# IRIS.net
KiCad netlist of a schematic drawn in EAGLE
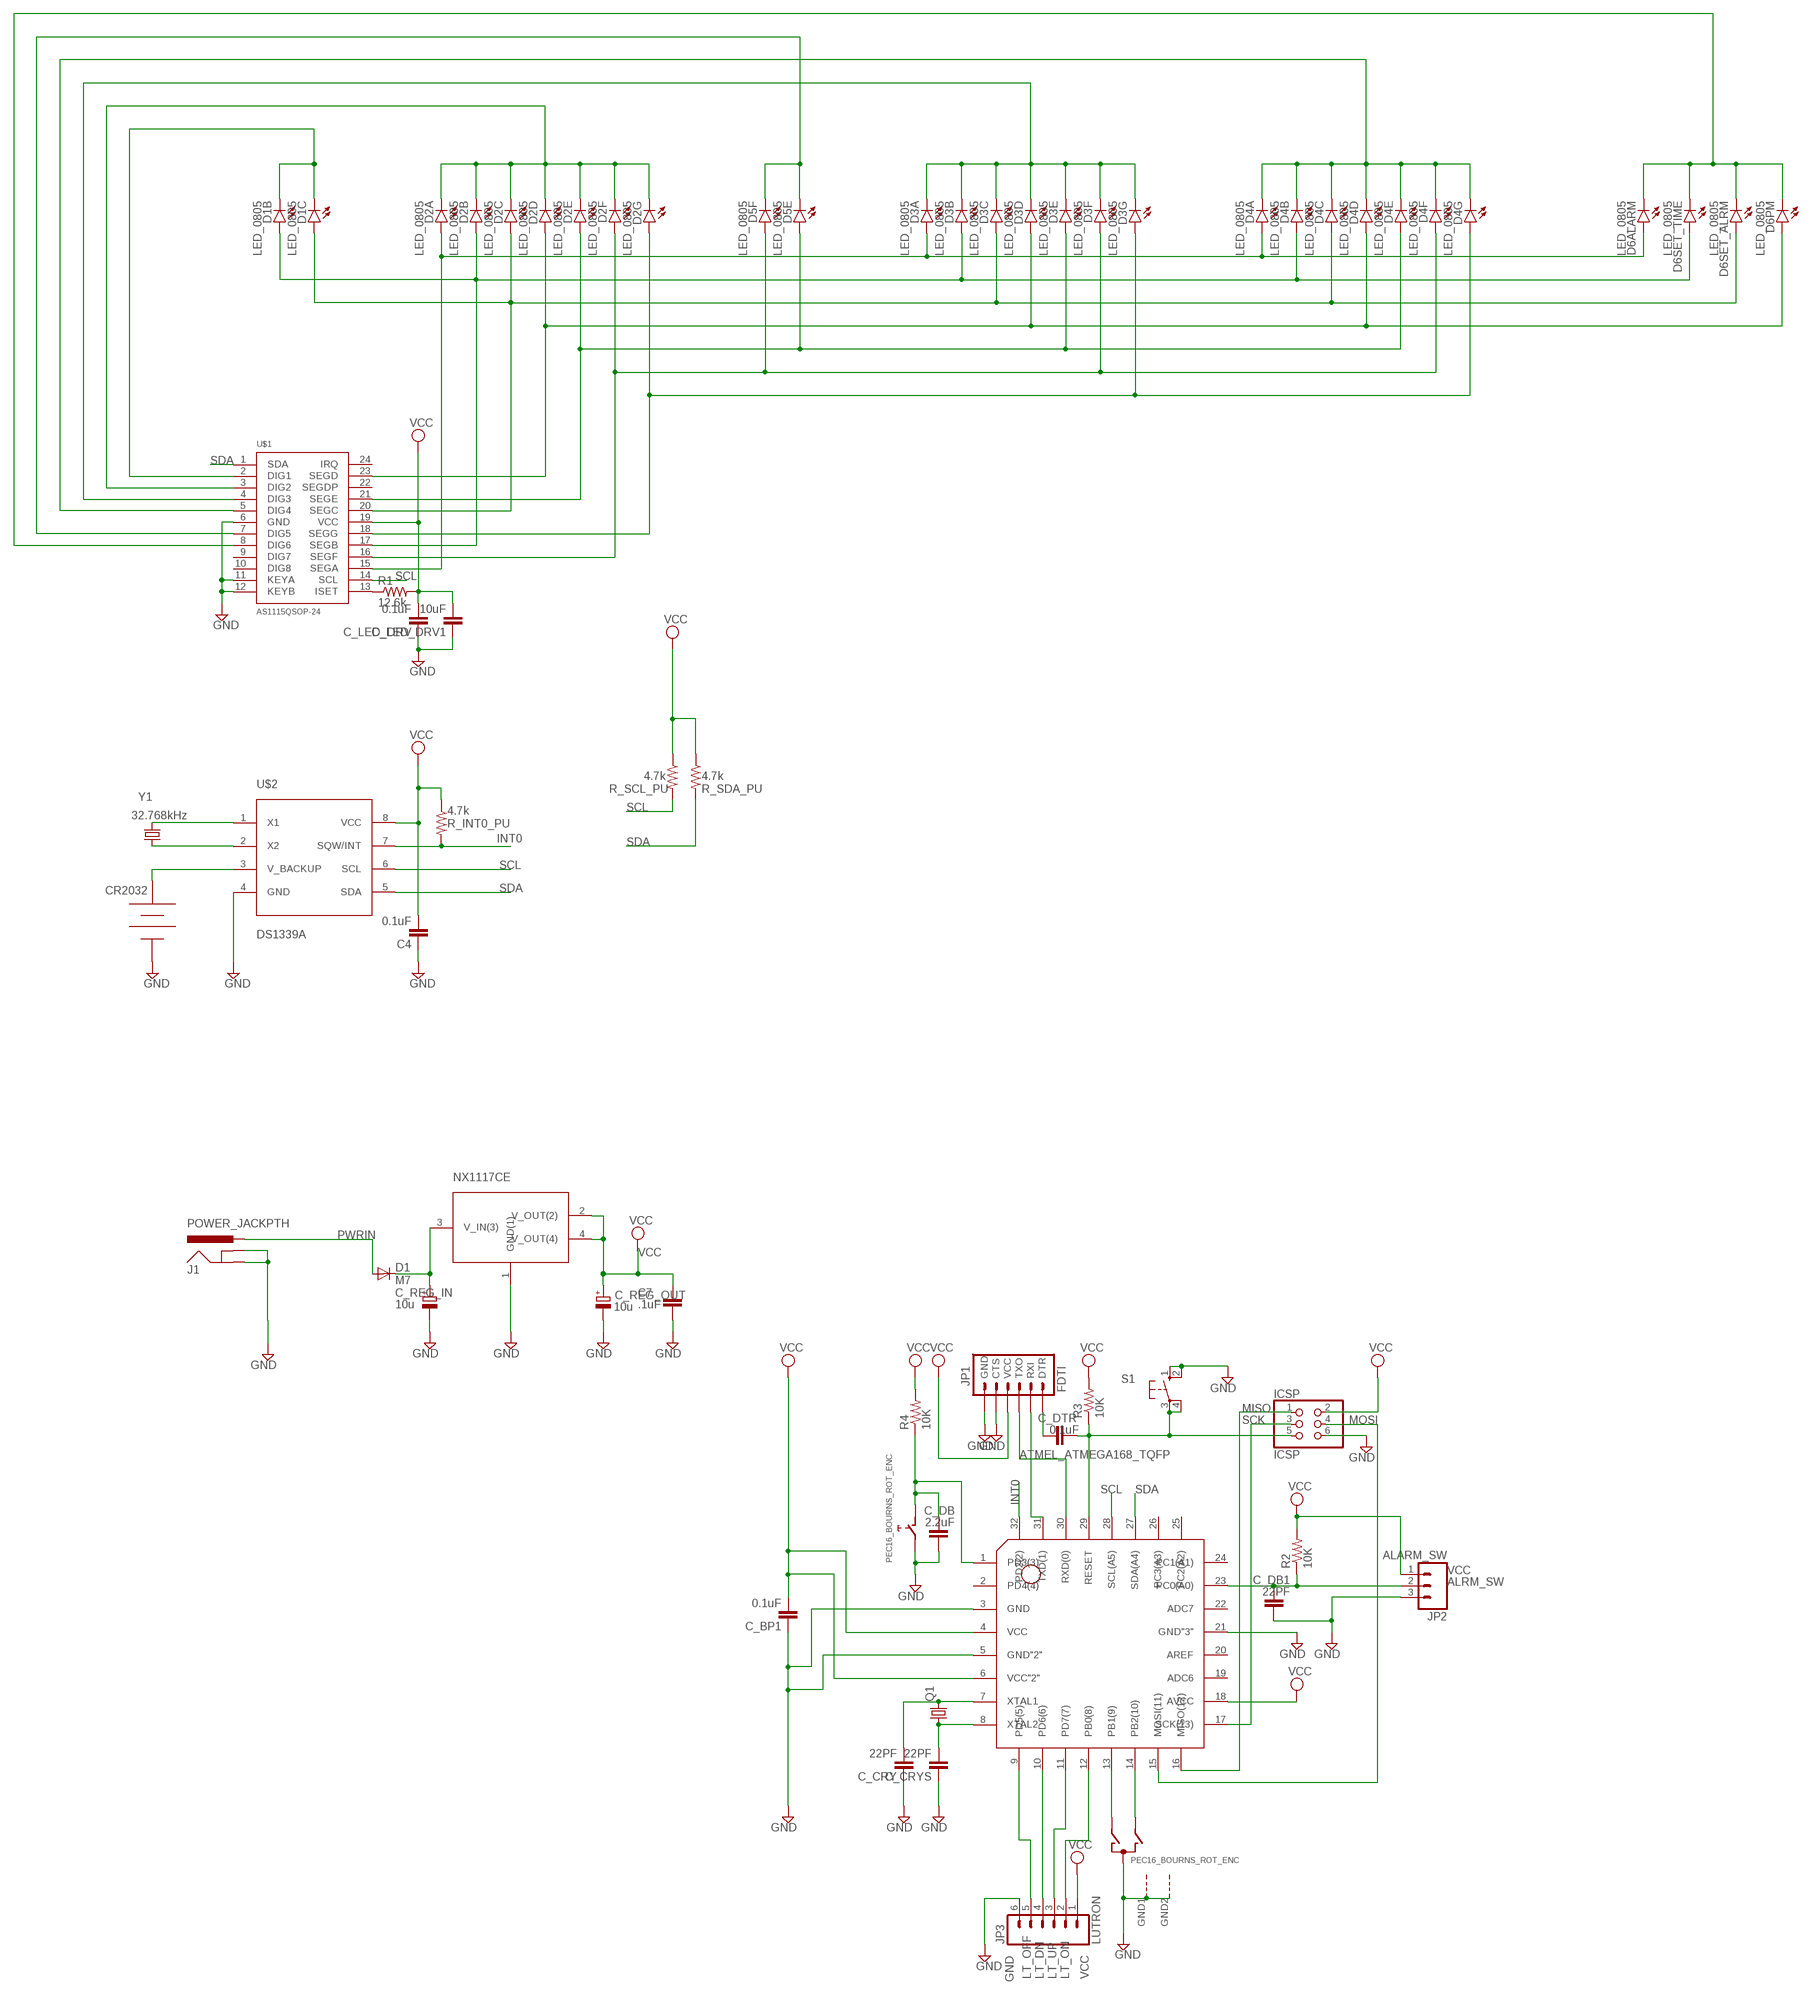
[diagram p0: schematic, sheet 1]

(export (version "E")
  (design (tool "Eeschema 10.0.6"))
  (components
    (comp (ref "C4")
      (value "0.1uF")
      (footprint "eagle-import:0805")
      (libsource (lib "eagle-import") (part "CAP0805"))
    )
    (comp (ref "C7")
      (value ".1uF")
      (footprint "eagle-import:C0603-ROUND")
      (libsource (lib "eagle-import") (part "C-EU0603-RND"))
    )
    (comp (ref "C_BP1")
      (value "0.1uF")
      (footprint "eagle-import:0805")
      (libsource (lib "eagle-import") (part "CAP0805"))
    )
    (comp (ref "C_CRY")
      (value "22PF")
      (footprint "eagle-import:0805")
      (libsource (lib "eagle-import") (part "CAP0805"))
    )
    (comp (ref "C_CRYS")
      (value "22PF")
      (footprint "eagle-import:0805")
      (libsource (lib "eagle-import") (part "CAP0805"))
    )
    (comp (ref "C_DB")
      (value "2.2uF")
      (footprint "eagle-import:0805")
      (libsource (lib "eagle-import") (part "CAP0805"))
    )
    (comp (ref "C_DB1")
      (value "22PF")
      (footprint "eagle-import:0805")
      (libsource (lib "eagle-import") (part "CAP0805"))
    )
    (comp (ref "C_DTR")
      (value "0.1uF")
      (footprint "eagle-import:0805")
      (libsource (lib "eagle-import") (part "CAP0805"))
    )
    (comp (ref "C_LED_DRV")
      (value "0.1uF")
      (footprint "eagle-import:0805")
      (libsource (lib "eagle-import") (part "CAP0805"))
    )
    (comp (ref "C_LED_DRV1")
      (value "10uF")
      (footprint "eagle-import:0805")
      (libsource (lib "eagle-import") (part "CAP0805"))
    )
    (comp (ref "C_REG_IN")
      (value "10u")
      (footprint "eagle-import:PANASONIC_D")
      (libsource (lib "eagle-import") (part "CPOL-EUD"))
    )
    (comp (ref "C_REG_OUT")
      (value "10u")
      (footprint "eagle-import:PANASONIC_D")
      (libsource (lib "eagle-import") (part "CPOL-EUD"))
    )
    (comp (ref "D1")
      (value "M7")
      (footprint "eagle-import:SMB")
      (libsource (lib "eagle-import") (part "DIODE-SMB"))
    )
    (comp (ref "D1B")
      (value "LED_0805")
      (footprint "eagle-import:LED_0805")
      (libsource (lib "eagle-import") (part "LED_0805"))
    )
    (comp (ref "D1C")
      (value "LED_0805")
      (footprint "eagle-import:LED_0805")
      (libsource (lib "eagle-import") (part "LED_0805"))
    )
    (comp (ref "D2A")
      (value "LED_0805")
      (footprint "eagle-import:LED_0805")
      (libsource (lib "eagle-import") (part "LED_0805"))
    )
    (comp (ref "D2B")
      (value "LED_0805")
      (footprint "eagle-import:LED_0805")
      (libsource (lib "eagle-import") (part "LED_0805"))
    )
    (comp (ref "D2C")
      (value "LED_0805")
      (footprint "eagle-import:LED_0805")
      (libsource (lib "eagle-import") (part "LED_0805"))
    )
    (comp (ref "D2D")
      (value "LED_0805")
      (footprint "eagle-import:LED_0805")
      (libsource (lib "eagle-import") (part "LED_0805"))
    )
    (comp (ref "D2E")
      (value "LED_0805")
      (footprint "eagle-import:LED_0805")
      (libsource (lib "eagle-import") (part "LED_0805"))
    )
    (comp (ref "D2F")
      (value "LED_0805")
      (footprint "eagle-import:LED_0805")
      (libsource (lib "eagle-import") (part "LED_0805"))
    )
    (comp (ref "D2G")
      (value "LED_0805")
      (footprint "eagle-import:LED_0805")
      (libsource (lib "eagle-import") (part "LED_0805"))
    )
    (comp (ref "D3A")
      (value "LED_0805")
      (footprint "eagle-import:LED_0805")
      (libsource (lib "eagle-import") (part "LED_0805"))
    )
    (comp (ref "D3B")
      (value "LED_0805")
      (footprint "eagle-import:LED_0805")
      (libsource (lib "eagle-import") (part "LED_0805"))
    )
    (comp (ref "D3C")
      (value "LED_0805")
      (footprint "eagle-import:LED_0805")
      (libsource (lib "eagle-import") (part "LED_0805"))
    )
    (comp (ref "D3D")
      (value "LED_0805")
      (footprint "eagle-import:LED_0805")
      (libsource (lib "eagle-import") (part "LED_0805"))
    )
    (comp (ref "D3E")
      (value "LED_0805")
      (footprint "eagle-import:LED_0805")
      (libsource (lib "eagle-import") (part "LED_0805"))
    )
    (comp (ref "D3F")
      (value "LED_0805")
      (footprint "eagle-import:LED_0805")
      (libsource (lib "eagle-import") (part "LED_0805"))
    )
    (comp (ref "D3G")
      (value "LED_0805")
      (footprint "eagle-import:LED_0805")
      (libsource (lib "eagle-import") (part "LED_0805"))
    )
    (comp (ref "D4A")
      (value "LED_0805")
      (footprint "eagle-import:LED_0805")
      (libsource (lib "eagle-import") (part "LED_0805"))
    )
    (comp (ref "D4B")
      (value "LED_0805")
      (footprint "eagle-import:LED_0805")
      (libsource (lib "eagle-import") (part "LED_0805"))
    )
    (comp (ref "D4C")
      (value "LED_0805")
      (footprint "eagle-import:LED_0805")
      (libsource (lib "eagle-import") (part "LED_0805"))
    )
    (comp (ref "D4D")
      (value "LED_0805")
      (footprint "eagle-import:LED_0805")
      (libsource (lib "eagle-import") (part "LED_0805"))
    )
    (comp (ref "D4E")
      (value "LED_0805")
      (footprint "eagle-import:LED_0805")
      (libsource (lib "eagle-import") (part "LED_0805"))
    )
    (comp (ref "D4F")
      (value "LED_0805")
      (footprint "eagle-import:LED_0805")
      (libsource (lib "eagle-import") (part "LED_0805"))
    )
    (comp (ref "D4G")
      (value "LED_0805")
      (footprint "eagle-import:LED_0805")
      (libsource (lib "eagle-import") (part "LED_0805"))
    )
    (comp (ref "D5E")
      (value "LED_0805")
      (footprint "eagle-import:LED_0805")
      (libsource (lib "eagle-import") (part "LED_0805"))
    )
    (comp (ref "D5F")
      (value "LED_0805")
      (footprint "eagle-import:LED_0805")
      (libsource (lib "eagle-import") (part "LED_0805"))
    )
    (comp (ref "D6ALARM")
      (value "LED_0805")
      (footprint "eagle-import:LED_0805")
      (libsource (lib "eagle-import") (part "LED_0805"))
    )
    (comp (ref "D6PM")
      (value "LED_0805")
      (footprint "eagle-import:LED_0805")
      (libsource (lib "eagle-import") (part "LED_0805"))
    )
    (comp (ref "D6SET_ALRM")
      (value "LED_0805")
      (footprint "eagle-import:LED_0805")
      (libsource (lib "eagle-import") (part "LED_0805"))
    )
    (comp (ref "D6SET_TIME")
      (value "LED_0805")
      (footprint "eagle-import:LED_0805")
      (libsource (lib "eagle-import") (part "LED_0805"))
    )
    (comp (ref "ICSP")
      (value "ICSP")
      (footprint "eagle-import:2X03")
      (libsource (lib "eagle-import") (part "PINHD-2X3"))
    )
    (comp (ref "J1")
      (value "POWER_JACKPTH")
      (footprint "eagle-import:POWER_JACK_PTH")
      (libsource (lib "eagle-import") (part "POWER_JACKPTH"))
    )
    (comp (ref "JP1")
      (value "FDTI")
      (footprint "eagle-import:1X06_LONGPADS")
      (libsource (lib "eagle-import") (part "ARDUINO_SERIAL_PROGRAMLONGPADS"))
    )
    (comp (ref "JP2")
      (value "ALARM_SW")
      (footprint "eagle-import:1X03_LONGPADS")
      (libsource (lib "eagle-import") (part "M03LONGPADS"))
    )
    (comp (ref "JP3")
      (value "LUTRON")
      (footprint "eagle-import:1X06_LONGPADS")
      (libsource (lib "eagle-import") (part "M06LONGPADS"))
    )
    (comp (ref "Q1")
      (value "CRYSTALHC49S")
      (footprint "eagle-import:HC49_S")
      (libsource (lib "eagle-import") (part "CRYSTALHC49S"))
    )
    (comp (ref "R1")
      (value "12.6k")
      (footprint "eagle-import:R0805")
      (libsource (lib "eagle-import") (part "R-US_R0805"))
    )
    (comp (ref "R2")
      (value "10K")
      (footprint "eagle-import:R0805")
      (libsource (lib "eagle-import") (part "R-US_R0805"))
    )
    (comp (ref "R3")
      (value "10K")
      (footprint "eagle-import:R0805")
      (libsource (lib "eagle-import") (part "R-US_R0805"))
    )
    (comp (ref "R4")
      (value "10K")
      (footprint "eagle-import:R0805")
      (libsource (lib "eagle-import") (part "R-US_R0805"))
    )
    (comp (ref "R_INT0_PU")
      (value "4.7k")
      (footprint "eagle-import:R0805")
      (libsource (lib "eagle-import") (part "R-US_R0805"))
    )
    (comp (ref "R_SCL_PU")
      (value "4.7k")
      (footprint "eagle-import:R0805")
      (libsource (lib "eagle-import") (part "R-US_R0805"))
    )
    (comp (ref "R_SDA_PU")
      (value "4.7k")
      (footprint "eagle-import:R0805")
      (libsource (lib "eagle-import") (part "R-US_R0805"))
    )
    (comp (ref "S1")
      (value "10-XX")
      (footprint "eagle-import:B3F-10XX")
      (fields (field (name "MPN") "B3F-1000"))
      (libsource (lib "eagle-import") (part "10-XX"))
    )
    (comp (ref "U$1")
      (value "AS1115QSOP-24")
      (footprint "eagle-import:SSOP24")
      (libsource (lib "eagle-import") (part "AS1115QSOP-24"))
    )
    (comp (ref "U$2")
      (value "DS1339A")
      (footprint "eagle-import:8_USOP")
      (libsource (lib "eagle-import") (part "DS1339A"))
    )
    (comp (ref "U$3")
      (value "CR2032")
      (footprint "eagle-import:CR2032")
      (libsource (lib "eagle-import") (part "CR2032"))
    )
    (comp (ref "U$4")
      (value "PEC16_BOURNS_ROT_ENC")
      (footprint "eagle-import:ENCODER_ROTARY")
      (libsource (lib "eagle-import") (part "PEC16_BOURNS_ROT_ENC"))
    )
    (comp (ref "U$5")
      (value "ATMEL_ATMEGA168_TQFP")
      (footprint "eagle-import:TQFP_32_ATMEGA168")
      (libsource (lib "eagle-import") (part "ATMEL_ATMEGA168_TQFP"))
    )
    (comp (ref "U$6")
      (value "NX1117CE")
      (footprint "eagle-import:LINEAR_REG_SOT223")
      (libsource (lib "eagle-import") (part "NX1117CE"))
    )
    (comp (ref "Y1")
      (value "32.768kHz")
      (footprint "eagle-import:CRYSTAL-32KHZ-SMD")
      (libsource (lib "eagle-import") (part "CRYSTAL32-SMD"))
    )
  )
  (nets
    (net (code "1") (name "/ALRM_SW") (class "Default")
      (node (ref "C_DB1") (pin "2") (pinfunction "2_2") (pintype "passive"))
      (node (ref "JP2") (pin "2") (pinfunction "2_2") (pintype "passive"))
      (node (ref "R2") (pin "1") (pinfunction "1_1") (pintype "passive"))
      (node (ref "U$5") (pin "23") (pinfunction "PC0(A0)_23") (pintype "bidirectional"))
    )
    (net (code "2") (name "/INT0") (class "Default")
      (node (ref "R_INT0_PU") (pin "2") (pinfunction "2_2") (pintype "passive"))
      (node (ref "U$2") (pin "7") (pinfunction "SQW/INT_7") (pintype "bidirectional"))
      (node (ref "U$5") (pin "32") (pinfunction "PD2(2)_32") (pintype "bidirectional"))
    )
    (net (code "3") (name "/LT_DN") (class "Default")
      (node (ref "JP3") (pin "4") (pinfunction "4_4") (pintype "passive"))
      (node (ref "U$5") (pin "10") (pinfunction "PD6(6)_10") (pintype "bidirectional"))
    )
    (net (code "4") (name "/LT_OFF") (class "Default")
      (node (ref "JP3") (pin "5") (pinfunction "5_5") (pintype "passive"))
      (node (ref "U$5") (pin "9") (pinfunction "PD5(5)_9") (pintype "bidirectional"))
    )
    (net (code "5") (name "/LT_ON") (class "Default")
      (node (ref "JP3") (pin "2") (pinfunction "2_2") (pintype "passive"))
      (node (ref "U$5") (pin "12") (pinfunction "PB0(8)_12") (pintype "bidirectional"))
    )
    (net (code "6") (name "/LT_UP") (class "Default")
      (node (ref "JP3") (pin "3") (pinfunction "3_3") (pintype "passive"))
      (node (ref "U$5") (pin "11") (pinfunction "PD7(7)_11") (pintype "bidirectional"))
    )
    (net (code "7") (name "/MISO") (class "Default")
      (node (ref "ICSP") (pin "1") (pinfunction "1_1") (pintype "passive"))
      (node (ref "U$5") (pin "16") (pinfunction "MISO(12)_16") (pintype "bidirectional"))
    )
    (net (code "8") (name "/MOSI") (class "Default")
      (node (ref "ICSP") (pin "4") (pinfunction "4_4") (pintype "passive"))
      (node (ref "U$5") (pin "15") (pinfunction "MOSI(11)_15") (pintype "bidirectional"))
    )
    (net (code "9") (name "/PWRIN") (class "Default")
      (node (ref "D1") (pin "A") (pinfunction "A_A") (pintype "passive"))
      (node (ref "J1") (pin "PWR") (pinfunction "PWR_PWR") (pintype "bidirectional"))
    )
    (net (code "10") (name "/SCK") (class "Default")
      (node (ref "ICSP") (pin "3") (pinfunction "3_3") (pintype "passive"))
      (node (ref "U$5") (pin "17") (pinfunction "SCK(13)_17") (pintype "bidirectional"))
    )
    (net (code "11") (name "/SCL") (class "Default")
      (node (ref "R_SCL_PU") (pin "2") (pinfunction "2_2") (pintype "passive"))
      (node (ref "U$1") (pin "14") (pinfunction "SCL_14") (pintype "bidirectional"))
      (node (ref "U$2") (pin "6") (pinfunction "SCL_6") (pintype "bidirectional"))
      (node (ref "U$5") (pin "28") (pinfunction "SCL(A5)_28") (pintype "bidirectional"))
    )
    (net (code "12") (name "/SDA") (class "Default")
      (node (ref "R_SDA_PU") (pin "2") (pinfunction "2_2") (pintype "passive"))
      (node (ref "U$1") (pin "1") (pinfunction "SDA_1") (pintype "bidirectional"))
      (node (ref "U$2") (pin "5") (pinfunction "SDA_5") (pintype "bidirectional"))
      (node (ref "U$5") (pin "27") (pinfunction "SDA(A4)_27") (pintype "bidirectional"))
    )
    (net (code "13") (name "GND") (class "Default")
      (node (ref "C4") (pin "1") (pinfunction "1_1") (pintype "passive"))
      (node (ref "C7") (pin "1") (pinfunction "1_1") (pintype "passive"))
      (node (ref "C_BP1") (pin "1") (pinfunction "1_1") (pintype "passive"))
      (node (ref "C_CRY") (pin "1") (pinfunction "1_1") (pintype "passive"))
      (node (ref "C_CRYS") (pin "1") (pinfunction "1_1") (pintype "passive"))
      (node (ref "C_DB") (pin "1") (pinfunction "1_1") (pintype "passive"))
      (node (ref "C_DB1") (pin "1") (pinfunction "1_1") (pintype "passive"))
      (node (ref "C_LED_DRV") (pin "1") (pinfunction "1_1") (pintype "passive"))
      (node (ref "C_LED_DRV1") (pin "1") (pinfunction "1_1") (pintype "passive"))
      (node (ref "C_REG_IN") (pin "-") (pinfunction "-_-") (pintype "passive"))
      (node (ref "C_REG_OUT") (pin "-") (pinfunction "-_-") (pintype "passive"))
      (node (ref "ICSP") (pin "6") (pinfunction "6_6") (pintype "passive"))
      (node (ref "J1") (pin "GND") (pinfunction "GND_GND") (pintype "bidirectional"))
      (node (ref "J1") (pin "GNDBREAK") (pinfunction "GNDBREAK_GNDBREAK") (pintype "bidirectional"))
      (node (ref "JP1") (pin "5") (pinfunction "CTS_5") (pintype "passive"))
      (node (ref "JP1") (pin "6") (pinfunction "GND_6") (pintype "passive"))
      (node (ref "JP2") (pin "3") (pinfunction "3_3") (pintype "passive"))
      (node (ref "JP3") (pin "6") (pinfunction "6_6") (pintype "passive"))
      (node (ref "S1") (pin "1") (pinfunction "S_1") (pintype "passive"))
      (node (ref "S1") (pin "2") (pinfunction "S1_2") (pintype "passive"))
      (node (ref "U$1") (pin "11") (pinfunction "KEYA_11") (pintype "bidirectional"))
      (node (ref "U$1") (pin "12") (pinfunction "KEYB_12") (pintype "bidirectional"))
      (node (ref "U$1") (pin "6") (pinfunction "GND_6") (pintype "power_in"))
      (node (ref "U$2") (pin "4") (pinfunction "GND_4") (pintype "power_in"))
      (node (ref "U$3") (pin "GND") (pinfunction "GND_GND") (pintype "power_in"))
      (node (ref "U$4") (pin "C") (pinfunction "C_C") (pintype "passive"))
      (node (ref "U$4") (pin "E") (pinfunction "2_E") (pintype "passive"))
      (node (ref "U$4") (pin "GND1") (pinfunction "G_GND1") (pintype "passive"))
      (node (ref "U$4") (pin "GND2") (pinfunction "G_GND2") (pintype "passive"))
      (node (ref "U$5") (pin "21") (pinfunction "GND\"3\"_21") (pintype "power_in"))
      (node (ref "U$5") (pin "3") (pinfunction "GND_3") (pintype "power_in"))
      (node (ref "U$5") (pin "5") (pinfunction "GND\"2\"_5") (pintype "power_in"))
      (node (ref "U$6") (pin "1") (pinfunction "GND(1)_1") (pintype "power_in"))
    )
    (net (code "14") (name "Net-(JP1-DTR)") (class "Default")
      (node (ref "C_DTR") (pin "2") (pinfunction "2_2") (pintype "passive"))
      (node (ref "JP1") (pin "1") (pinfunction "DTR_1") (pintype "passive"))
    )
    (net (code "15") (name "Net-(JP1-RXI)") (class "Default")
      (node (ref "JP1") (pin "2") (pinfunction "RXI_2") (pintype "passive"))
      (node (ref "U$5") (pin "31") (pinfunction "TXD(1)_31") (pintype "bidirectional"))
    )
    (net (code "16") (name "Net-(JP1-TXO)") (class "Default")
      (node (ref "JP1") (pin "3") (pinfunction "TXO_3") (pintype "passive"))
      (node (ref "U$5") (pin "30") (pinfunction "RXD(0)_30") (pintype "bidirectional"))
    )
    (net (code "17") (name "Net-(S1-P)") (class "Default")
      (node (ref "C_DTR") (pin "1") (pinfunction "1_1") (pintype "passive"))
      (node (ref "ICSP") (pin "5") (pinfunction "5_5") (pintype "passive"))
      (node (ref "R3") (pin "1") (pinfunction "1_1") (pintype "passive"))
      (node (ref "S1") (pin "3") (pinfunction "P_3") (pintype "passive"))
      (node (ref "S1") (pin "4") (pinfunction "P1_4") (pintype "passive"))
      (node (ref "U$5") (pin "29") (pinfunction "RESET_29") (pintype "bidirectional"))
    )
    (net (code "18") (name "Net-(U$1-DIG1)") (class "Default")
      (node (ref "D1B") (pin "C") (pinfunction "C_C") (pintype "passive"))
      (node (ref "D1C") (pin "C") (pinfunction "C_C") (pintype "passive"))
      (node (ref "U$1") (pin "2") (pinfunction "DIG1_2") (pintype "bidirectional"))
    )
    (net (code "19") (name "Net-(U$1-DIG2)") (class "Default")
      (node (ref "D2A") (pin "C") (pinfunction "C_C") (pintype "passive"))
      (node (ref "D2B") (pin "C") (pinfunction "C_C") (pintype "passive"))
      (node (ref "D2C") (pin "C") (pinfunction "C_C") (pintype "passive"))
      (node (ref "D2D") (pin "C") (pinfunction "C_C") (pintype "passive"))
      (node (ref "D2E") (pin "C") (pinfunction "C_C") (pintype "passive"))
      (node (ref "D2F") (pin "C") (pinfunction "C_C") (pintype "passive"))
      (node (ref "D2G") (pin "C") (pinfunction "C_C") (pintype "passive"))
      (node (ref "U$1") (pin "3") (pinfunction "DIG2_3") (pintype "bidirectional"))
    )
    (net (code "20") (name "Net-(U$1-DIG3)") (class "Default")
      (node (ref "D3A") (pin "C") (pinfunction "C_C") (pintype "passive"))
      (node (ref "D3B") (pin "C") (pinfunction "C_C") (pintype "passive"))
      (node (ref "D3C") (pin "C") (pinfunction "C_C") (pintype "passive"))
      (node (ref "D3D") (pin "C") (pinfunction "C_C") (pintype "passive"))
      (node (ref "D3E") (pin "C") (pinfunction "C_C") (pintype "passive"))
      (node (ref "D3F") (pin "C") (pinfunction "C_C") (pintype "passive"))
      (node (ref "D3G") (pin "C") (pinfunction "C_C") (pintype "passive"))
      (node (ref "U$1") (pin "4") (pinfunction "DIG3_4") (pintype "bidirectional"))
    )
    (net (code "21") (name "Net-(U$1-DIG4)") (class "Default")
      (node (ref "D4A") (pin "C") (pinfunction "C_C") (pintype "passive"))
      (node (ref "D4B") (pin "C") (pinfunction "C_C") (pintype "passive"))
      (node (ref "D4C") (pin "C") (pinfunction "C_C") (pintype "passive"))
      (node (ref "D4D") (pin "C") (pinfunction "C_C") (pintype "passive"))
      (node (ref "D4E") (pin "C") (pinfunction "C_C") (pintype "passive"))
      (node (ref "D4F") (pin "C") (pinfunction "C_C") (pintype "passive"))
      (node (ref "D4G") (pin "C") (pinfunction "C_C") (pintype "passive"))
      (node (ref "U$1") (pin "5") (pinfunction "DIG4_5") (pintype "bidirectional"))
    )
    (net (code "22") (name "Net-(U$1-DIG5)") (class "Default")
      (node (ref "D5E") (pin "C") (pinfunction "C_C") (pintype "passive"))
      (node (ref "D5F") (pin "C") (pinfunction "C_C") (pintype "passive"))
      (node (ref "U$1") (pin "7") (pinfunction "DIG5_7") (pintype "bidirectional"))
    )
    (net (code "23") (name "Net-(U$1-DIG6)") (class "Default")
      (node (ref "D6ALARM") (pin "C") (pinfunction "C_C") (pintype "passive"))
      (node (ref "D6PM") (pin "C") (pinfunction "C_C") (pintype "passive"))
      (node (ref "D6SET_ALRM") (pin "C") (pinfunction "C_C") (pintype "passive"))
      (node (ref "D6SET_TIME") (pin "C") (pinfunction "C_C") (pintype "passive"))
      (node (ref "U$1") (pin "8") (pinfunction "DIG6_8") (pintype "bidirectional"))
    )
    (net (code "24") (name "Net-(U$1-ISET)") (class "Default")
      (node (ref "R1") (pin "1") (pinfunction "1_1") (pintype "passive"))
      (node (ref "U$1") (pin "13") (pinfunction "ISET_13") (pintype "bidirectional"))
    )
    (net (code "25") (name "Net-(U$1-SEGA)") (class "Default")
      (node (ref "D2A") (pin "A") (pinfunction "A_A") (pintype "passive"))
      (node (ref "D3A") (pin "A") (pinfunction "A_A") (pintype "passive"))
      (node (ref "D4A") (pin "A") (pinfunction "A_A") (pintype "passive"))
      (node (ref "D6ALARM") (pin "A") (pinfunction "A_A") (pintype "passive"))
      (node (ref "U$1") (pin "15") (pinfunction "SEGA_15") (pintype "bidirectional"))
    )
    (net (code "26") (name "Net-(U$1-SEGB)") (class "Default")
      (node (ref "D1B") (pin "A") (pinfunction "A_A") (pintype "passive"))
      (node (ref "D2B") (pin "A") (pinfunction "A_A") (pintype "passive"))
      (node (ref "D3B") (pin "A") (pinfunction "A_A") (pintype "passive"))
      (node (ref "D4B") (pin "A") (pinfunction "A_A") (pintype "passive"))
      (node (ref "D6SET_TIME") (pin "A") (pinfunction "A_A") (pintype "passive"))
      (node (ref "U$1") (pin "17") (pinfunction "SEGB_17") (pintype "bidirectional"))
    )
    (net (code "27") (name "Net-(U$1-SEGC)") (class "Default")
      (node (ref "D1C") (pin "A") (pinfunction "A_A") (pintype "passive"))
      (node (ref "D2C") (pin "A") (pinfunction "A_A") (pintype "passive"))
      (node (ref "D3C") (pin "A") (pinfunction "A_A") (pintype "passive"))
      (node (ref "D4C") (pin "A") (pinfunction "A_A") (pintype "passive"))
      (node (ref "D6SET_ALRM") (pin "A") (pinfunction "A_A") (pintype "passive"))
      (node (ref "U$1") (pin "20") (pinfunction "SEGC_20") (pintype "bidirectional"))
    )
    (net (code "28") (name "Net-(U$1-SEGD)") (class "Default")
      (node (ref "D2D") (pin "A") (pinfunction "A_A") (pintype "passive"))
      (node (ref "D3D") (pin "A") (pinfunction "A_A") (pintype "passive"))
      (node (ref "D4D") (pin "A") (pinfunction "A_A") (pintype "passive"))
      (node (ref "D6PM") (pin "A") (pinfunction "A_A") (pintype "passive"))
      (node (ref "U$1") (pin "23") (pinfunction "SEGD_23") (pintype "bidirectional"))
    )
    (net (code "29") (name "Net-(U$1-SEGE)") (class "Default")
      (node (ref "D2E") (pin "A") (pinfunction "A_A") (pintype "passive"))
      (node (ref "D3E") (pin "A") (pinfunction "A_A") (pintype "passive"))
      (node (ref "D4E") (pin "A") (pinfunction "A_A") (pintype "passive"))
      (node (ref "D5E") (pin "A") (pinfunction "A_A") (pintype "passive"))
      (node (ref "U$1") (pin "21") (pinfunction "SEGE_21") (pintype "bidirectional"))
    )
    (net (code "30") (name "Net-(U$1-SEGF)") (class "Default")
      (node (ref "D2F") (pin "A") (pinfunction "A_A") (pintype "passive"))
      (node (ref "D3F") (pin "A") (pinfunction "A_A") (pintype "passive"))
      (node (ref "D4F") (pin "A") (pinfunction "A_A") (pintype "passive"))
      (node (ref "D5F") (pin "A") (pinfunction "A_A") (pintype "passive"))
      (node (ref "U$1") (pin "16") (pinfunction "SEGF_16") (pintype "bidirectional"))
    )
    (net (code "31") (name "Net-(U$1-SEGG)") (class "Default")
      (node (ref "D2G") (pin "A") (pinfunction "A_A") (pintype "passive"))
      (node (ref "D3G") (pin "A") (pinfunction "A_A") (pintype "passive"))
      (node (ref "D4G") (pin "A") (pinfunction "A_A") (pintype "passive"))
      (node (ref "U$1") (pin "18") (pinfunction "SEGG_18") (pintype "bidirectional"))
    )
    (net (code "32") (name "Net-(U$2-V_BACKUP)") (class "Default")
      (node (ref "U$2") (pin "3") (pinfunction "V_BACKUP_3") (pintype "bidirectional"))
      (node (ref "U$3") (pin "V+") (pinfunction "V+_V+") (pintype "power_in"))
    )
    (net (code "33") (name "Net-(U$2-X1)") (class "Default")
      (node (ref "U$2") (pin "1") (pinfunction "X1_1") (pintype "bidirectional"))
      (node (ref "Y1") (pin "X2") (pinfunction "2_X2") (pintype "passive"))
    )
    (net (code "34") (name "Net-(U$2-X2)") (class "Default")
      (node (ref "U$2") (pin "2") (pinfunction "X2_2") (pintype "bidirectional"))
      (node (ref "Y1") (pin "X1") (pinfunction "1_X1") (pintype "passive"))
    )
    (net (code "35") (name "Net-(U$4D-1)") (class "Default")
      (node (ref "C_DB") (pin "2") (pinfunction "2_2") (pintype "passive"))
      (node (ref "R4") (pin "1") (pinfunction "1_1") (pintype "passive"))
      (node (ref "U$4") (pin "D") (pinfunction "1_D") (pintype "passive"))
      (node (ref "U$5") (pin "1") (pinfunction "PD3(3)_1") (pintype "bidirectional"))
    )
    (net (code "36") (name "Net-(U$5-PB1(9))") (class "Default")
      (node (ref "U$4") (pin "A") (pinfunction "A_A") (pintype "passive"))
      (node (ref "U$5") (pin "13") (pinfunction "PB1(9)_13") (pintype "bidirectional"))
    )
    (net (code "37") (name "Net-(U$5-PB2(10))") (class "Default")
      (node (ref "U$4") (pin "B") (pinfunction "B_B") (pintype "passive"))
      (node (ref "U$5") (pin "14") (pinfunction "PB2(10)_14") (pintype "bidirectional"))
    )
    (net (code "38") (name "Net-(U$5-XTAL1)") (class "Default")
      (node (ref "C_CRY") (pin "2") (pinfunction "2_2") (pintype "passive"))
      (node (ref "Q1") (pin "2") (pinfunction "2_2") (pintype "passive"))
      (node (ref "U$5") (pin "7") (pinfunction "XTAL1_7") (pintype "bidirectional"))
    )
    (net (code "39") (name "Net-(U$5-XTAL2)") (class "Default")
      (node (ref "C_CRYS") (pin "2") (pinfunction "2_2") (pintype "passive"))
      (node (ref "Q1") (pin "1") (pinfunction "1_1") (pintype "passive"))
      (node (ref "U$5") (pin "8") (pinfunction "XTAL2_8") (pintype "bidirectional"))
    )
    (net (code "40") (name "Net-(U$6-V_IN(3))") (class "Default")
      (node (ref "C_REG_IN") (pin "+") (pinfunction "+_+") (pintype "passive"))
      (node (ref "D1") (pin "C") (pinfunction "C_C") (pintype "passive"))
      (node (ref "U$6") (pin "3") (pinfunction "V_IN(3)_3") (pintype "power_in"))
    )
    (net (code "41") (name "VCC") (class "Default")
      (node (ref "C4") (pin "2") (pinfunction "2_2") (pintype "passive"))
      (node (ref "C7") (pin "2") (pinfunction "2_2") (pintype "passive"))
      (node (ref "C_BP1") (pin "2") (pinfunction "2_2") (pintype "passive"))
      (node (ref "C_LED_DRV") (pin "2") (pinfunction "2_2") (pintype "passive"))
      (node (ref "C_LED_DRV1") (pin "2") (pinfunction "2_2") (pintype "passive"))
      (node (ref "C_REG_OUT") (pin "+") (pinfunction "+_+") (pintype "passive"))
      (node (ref "ICSP") (pin "2") (pinfunction "2_2") (pintype "passive"))
      (node (ref "JP1") (pin "4") (pinfunction "VCC_4") (pintype "passive"))
      (node (ref "JP2") (pin "1") (pinfunction "1_1") (pintype "passive"))
      (node (ref "JP3") (pin "1") (pinfunction "1_1") (pintype "passive"))
      (node (ref "R1") (pin "2") (pinfunction "2_2") (pintype "passive"))
      (node (ref "R2") (pin "2") (pinfunction "2_2") (pintype "passive"))
      (node (ref "R3") (pin "2") (pinfunction "2_2") (pintype "passive"))
      (node (ref "R4") (pin "2") (pinfunction "2_2") (pintype "passive"))
      (node (ref "R_INT0_PU") (pin "1") (pinfunction "1_1") (pintype "passive"))
      (node (ref "R_SCL_PU") (pin "1") (pinfunction "1_1") (pintype "passive"))
      (node (ref "R_SDA_PU") (pin "1") (pinfunction "1_1") (pintype "passive"))
      (node (ref "U$1") (pin "19") (pinfunction "VCC_19") (pintype "power_in"))
      (node (ref "U$2") (pin "8") (pinfunction "VCC_8") (pintype "power_in"))
      (node (ref "U$5") (pin "18") (pinfunction "AVCC_18") (pintype "power_in"))
      (node (ref "U$5") (pin "4") (pinfunction "VCC_4") (pintype "power_in"))
      (node (ref "U$5") (pin "6") (pinfunction "VCC\"2\"_6") (pintype "power_in"))
      (node (ref "U$6") (pin "2") (pinfunction "V_OUT(2)_2") (pintype "power_in"))
      (node (ref "U$6") (pin "4") (pinfunction "V_OUT(4)_4") (pintype "power_in"))
    )
    (net (code "42") (name "unconnected-(U$1-DIG7-Pad9)") (class "Default")
      (node (ref "U$1") (pin "9") (pinfunction "DIG7_9") (pintype "bidirectional"))
    )
    (net (code "43") (name "unconnected-(U$1-DIG8-Pad10)") (class "Default")
      (node (ref "U$1") (pin "10") (pinfunction "DIG8_10") (pintype "bidirectional"))
    )
    (net (code "44") (name "unconnected-(U$1-IRQ-Pad24)") (class "Default")
      (node (ref "U$1") (pin "24") (pinfunction "IRQ_24") (pintype "bidirectional"))
    )
    (net (code "45") (name "unconnected-(U$1-SEGDP-Pad22)") (class "Default")
      (node (ref "U$1") (pin "22") (pinfunction "SEGDP_22") (pintype "bidirectional"))
    )
    (net (code "46") (name "unconnected-(U$5-ADC6-Pad19)") (class "Default")
      (node (ref "U$5") (pin "19") (pinfunction "ADC6_19") (pintype "bidirectional"))
    )
    (net (code "47") (name "unconnected-(U$5-ADC7-Pad22)") (class "Default")
      (node (ref "U$5") (pin "22") (pinfunction "ADC7_22") (pintype "bidirectional"))
    )
    (net (code "48") (name "unconnected-(U$5-AREF-Pad20)") (class "Default")
      (node (ref "U$5") (pin "20") (pinfunction "AREF_20") (pintype "bidirectional"))
    )
    (net (code "49") (name "unconnected-(U$5-PC1(A1)-Pad24)") (class "Default")
      (node (ref "U$5") (pin "24") (pinfunction "PC1(A1)_24") (pintype "bidirectional"))
    )
    (net (code "50") (name "unconnected-(U$5-PC2(A2)-Pad25)") (class "Default")
      (node (ref "U$5") (pin "25") (pinfunction "PC2(A2)_25") (pintype "bidirectional"))
    )
    (net (code "51") (name "unconnected-(U$5-PC3(A3)-Pad26)") (class "Default")
      (node (ref "U$5") (pin "26") (pinfunction "PC3(A3)_26") (pintype "bidirectional"))
    )
    (net (code "52") (name "unconnected-(U$5-PD4(4)-Pad2)") (class "Default")
      (node (ref "U$5") (pin "2") (pinfunction "PD4(4)_2") (pintype "bidirectional"))
    )
  )
)
